# ALLPRINT-CAPBOARD-677512-HEAD-BOARD-COMM.net
KiCad netlist of a schematic drawn in Altium Designer
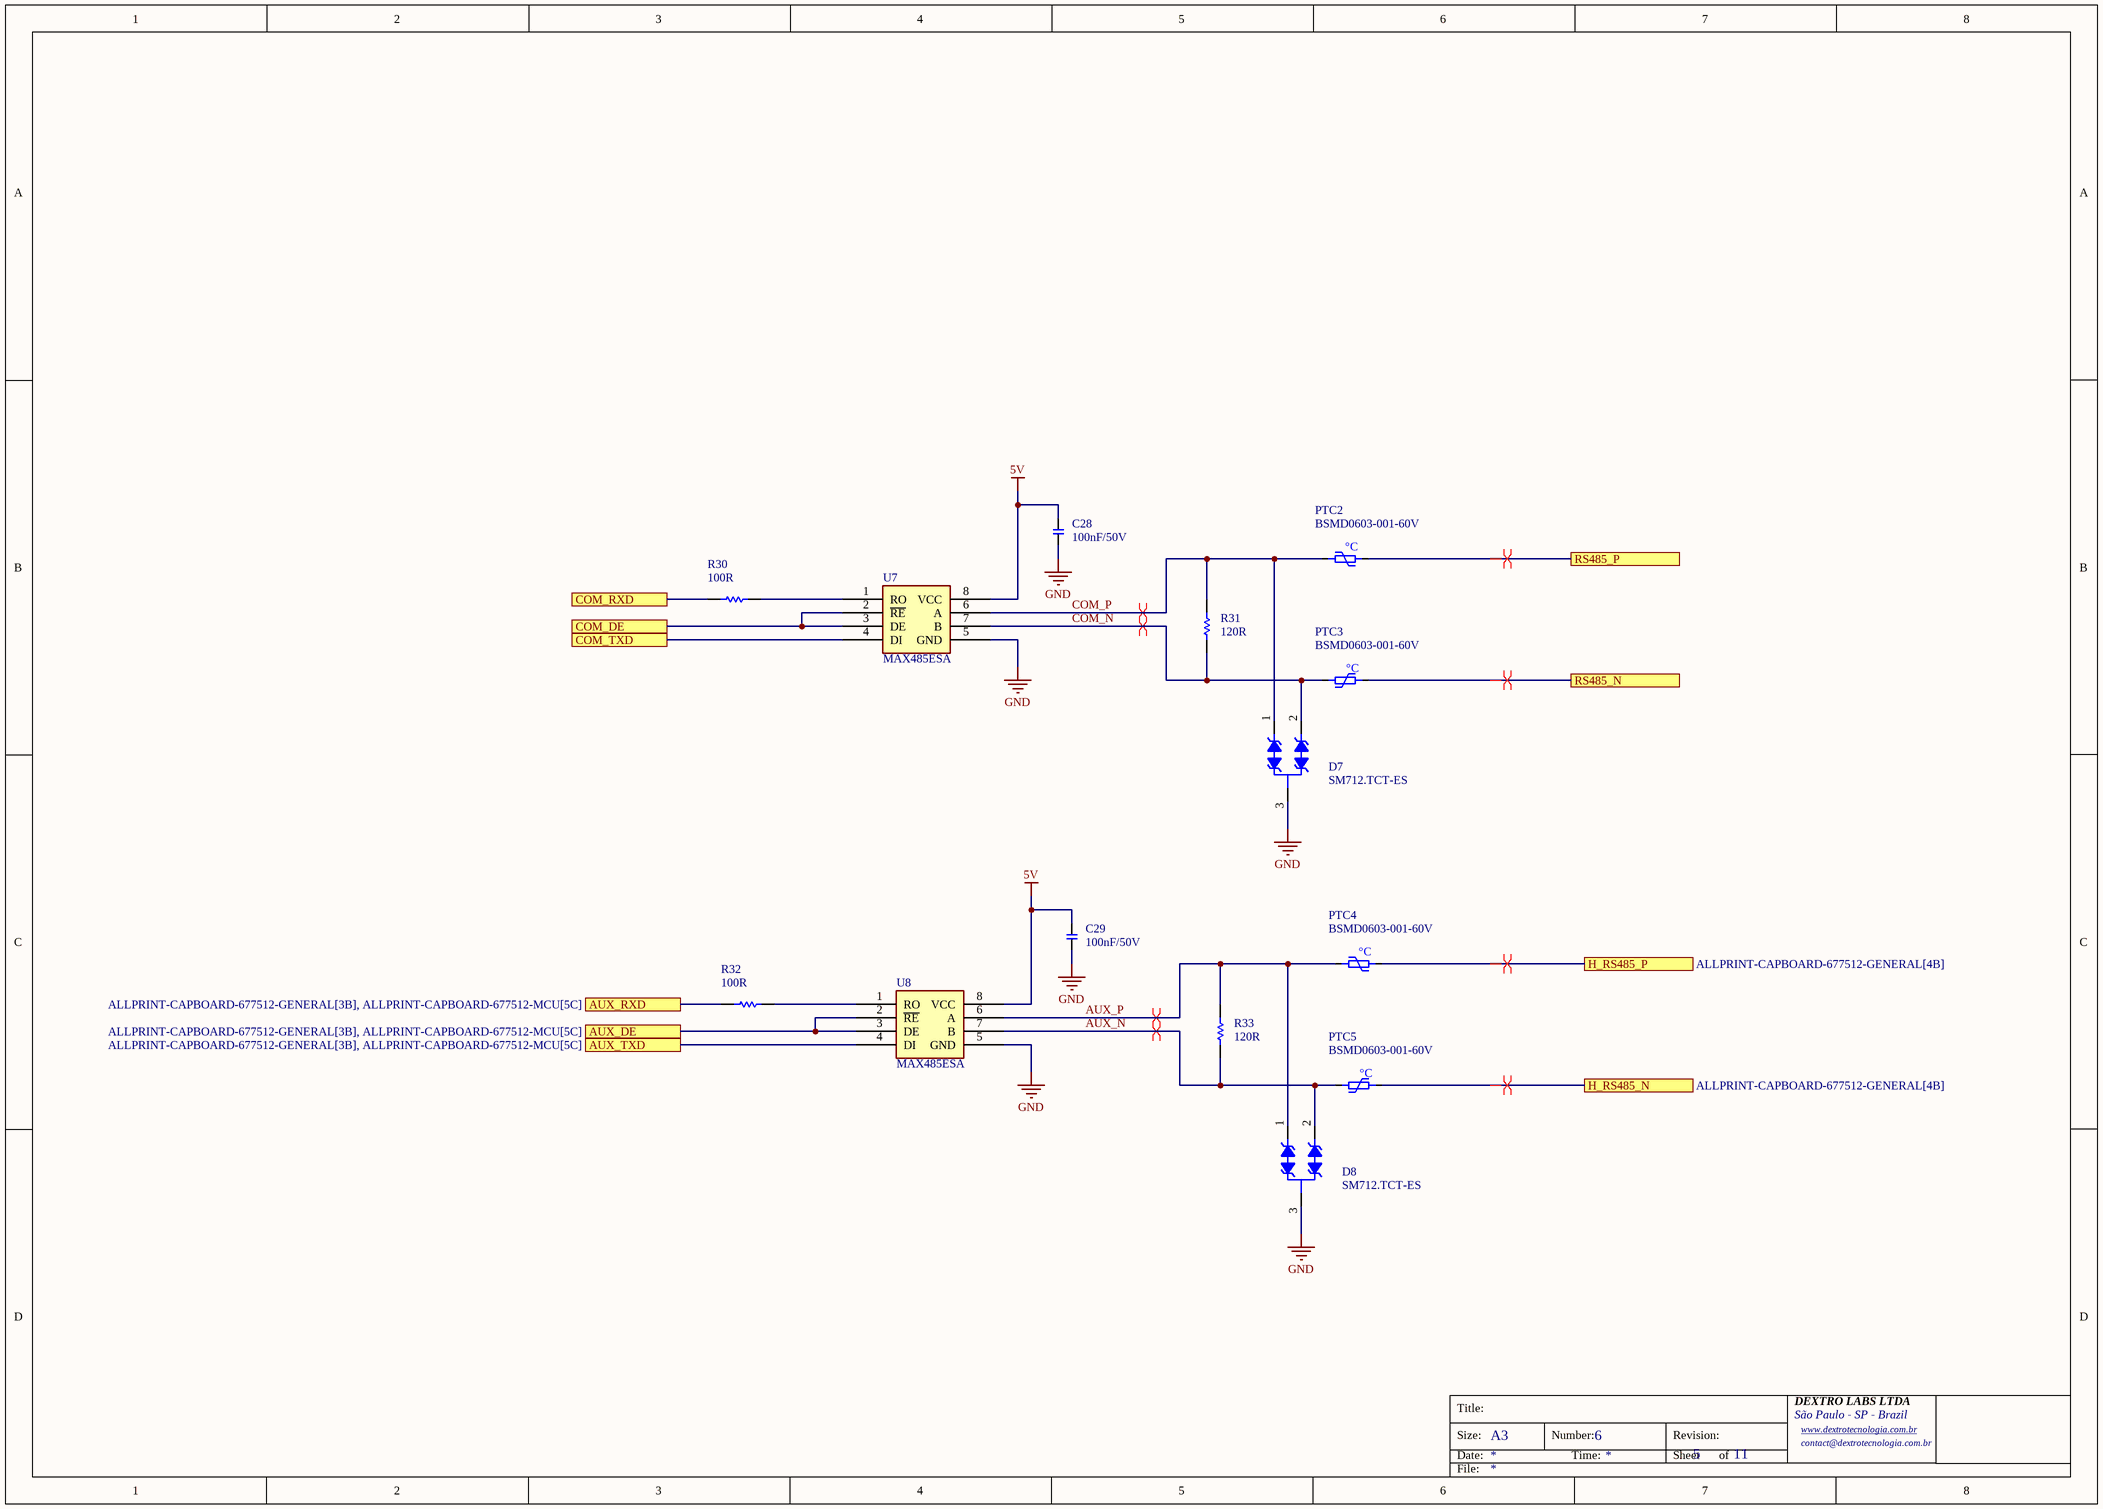
[diagram p0: ALLPRINT-CAPBOARD-677512-HEAD-BOARD-COMM.SchDoc]

(export (version "E")
  (design (tool "Eeschema 10.0.6"))
  (components
    (comp (ref "C28")
      (value "100nF/50V")
      (footprint "CAP-0603")
      (description "50V 100nF X7R ±10% 0603 Multilayer Ceramic Capacitors MLCC - SMD/SMT ROHS")
      (libsource (lib "dextro-labs") (part "CAP-100nF/50V-0603-X7R-MLCC"))
    )
    (comp (ref "C29")
      (value "100nF/50V")
      (footprint "CAP-0603")
      (description "50V 100nF X7R ±10% 0603 Multilayer Ceramic Capacitors MLCC - SMD/SMT ROHS")
      (libsource (lib "dextro-labs") (part "CAP-100nF/50V-0603-X7R-MLCC"))
    )
    (comp (ref "D7")
      (value "SM712.TCT-ES")
      (footprint "SOT23-3")
      (description "400W@8/20us Bidirectional SOT-23 ESD and Surge Protection (TVS/ESD) ROHS")
      (libsource (lib "dextro-labs") (part "SM712.TCT-ES"))
    )
    (comp (ref "D8")
      (value "SM712.TCT-ES")
      (footprint "SOT23-3")
      (description "400W@8/20us Bidirectional SOT-23 ESD and Surge Protection (TVS/ESD) ROHS")
      (libsource (lib "dextro-labs") (part "SM712.TCT-ES"))
    )
    (comp (ref "PTC2")
      (value "BSMD0603-001-60V")
      (footprint "PTC-0603")
      (description "60V 10mA 20A 50mA 15Ω 0603 PTC Resettable Fuses ROHS")
      (libsource (lib "dextro-labs") (part "PTC-FUSE-60V-10mA-0603"))
    )
    (comp (ref "PTC3")
      (value "BSMD0603-001-60V")
      (footprint "PTC-0603")
      (description "60V 10mA 20A 50mA 15Ω 0603 PTC Resettable Fuses ROHS")
      (libsource (lib "dextro-labs") (part "PTC-FUSE-60V-10mA-0603"))
    )
    (comp (ref "PTC4")
      (value "BSMD0603-001-60V")
      (footprint "PTC-0603")
      (description "60V 10mA 20A 50mA 15Ω 0603 PTC Resettable Fuses ROHS")
      (libsource (lib "dextro-labs") (part "PTC-FUSE-60V-10mA-0603"))
    )
    (comp (ref "PTC5")
      (value "BSMD0603-001-60V")
      (footprint "PTC-0603")
      (description "60V 10mA 20A 50mA 15Ω 0603 PTC Resettable Fuses ROHS")
      (libsource (lib "dextro-labs") (part "PTC-FUSE-60V-10mA-0603"))
    )
    (comp (ref "R30")
      (value "100R")
      (footprint "RES-0603")
      (description "100mW Thick Film Resistor 75V ±100ppm/℃ ±1% 100Ω 0603 Chip Resistor - Surface Mount ROHS")
      (libsource (lib "dextro-labs") (part "RES-100R-1%-100mW-0603"))
    )
    (comp (ref "R31")
      (value "120R")
      (footprint "RES-1206")
      (description "120Ω ±1% 500mW 1206 Thick Film Resistor")
      (libsource (lib "dextro-labs") (part "RES-120R-1%-500mW-1206"))
    )
    (comp (ref "R32")
      (value "100R")
      (footprint "RES-0603")
      (description "100mW Thick Film Resistor 75V ±100ppm/℃ ±1% 100Ω 0603 Chip Resistor - Surface Mount ROHS")
      (libsource (lib "dextro-labs") (part "RES-100R-1%-100mW-0603"))
    )
    (comp (ref "R33")
      (value "120R")
      (footprint "RES-1206")
      (description "120Ω ±1% 500mW 1206 Thick Film Resistor")
      (libsource (lib "dextro-labs") (part "RES-120R-1%-500mW-1206"))
    )
    (comp (ref "U7")
      (value "MAX485ESA")
      (footprint "SOIC-08")
      (description "Low-Power, Slew-Rate-Limited RS-485/RS-422 Transceivers")
      (libsource (lib "dextro-labs") (part "MAX485ESA"))
    )
    (comp (ref "U8")
      (value "MAX485ESA")
      (footprint "SOIC-08")
      (description "Low-Power, Slew-Rate-Limited RS-485/RS-422 Transceivers")
      (libsource (lib "dextro-labs") (part "MAX485ESA"))
    )
  )
  (nets
    (net (code "1") (name "/AUX_DE") (class "Default")
      (node (ref "U8") (pin "2") (pinfunction "~{RE}_2") (pintype "passive"))
      (node (ref "U8") (pin "3") (pinfunction "DE_3") (pintype "passive"))
    )
    (net (code "2") (name "/AUX_N") (class "Default")
      (node (ref "D8") (pin "2") (pinfunction "A2_2") (pintype "passive"))
      (node (ref "PTC5") (pin "2") (pinfunction "2_2") (pintype "passive"))
      (node (ref "R33") (pin "1") (pinfunction "1_1") (pintype "passive"))
      (node (ref "U8") (pin "7") (pinfunction "B_7") (pintype "passive"))
    )
    (net (code "3") (name "/AUX_P") (class "Default")
      (node (ref "D8") (pin "1") (pinfunction "A1_1") (pintype "passive"))
      (node (ref "PTC4") (pin "1") (pinfunction "1_1") (pintype "passive"))
      (node (ref "R33") (pin "2") (pinfunction "2_2") (pintype "passive"))
      (node (ref "U8") (pin "6") (pinfunction "A_6") (pintype "passive"))
    )
    (net (code "4") (name "/AUX_RXD") (class "Default")
      (node (ref "R32") (pin "1") (pinfunction "1_1") (pintype "passive"))
    )
    (net (code "5") (name "/AUX_TXD") (class "Default")
      (node (ref "U8") (pin "4") (pinfunction "DI_4") (pintype "passive"))
    )
    (net (code "6") (name "/COM_DE") (class "Default")
      (node (ref "U7") (pin "2") (pinfunction "~{RE}_2") (pintype "passive"))
      (node (ref "U7") (pin "3") (pinfunction "DE_3") (pintype "passive"))
    )
    (net (code "7") (name "/COM_N") (class "Default")
      (node (ref "D7") (pin "2") (pinfunction "A2_2") (pintype "passive"))
      (node (ref "PTC3") (pin "2") (pinfunction "2_2") (pintype "passive"))
      (node (ref "R31") (pin "1") (pinfunction "1_1") (pintype "passive"))
      (node (ref "U7") (pin "7") (pinfunction "B_7") (pintype "passive"))
    )
    (net (code "8") (name "/COM_P") (class "Default")
      (node (ref "D7") (pin "1") (pinfunction "A1_1") (pintype "passive"))
      (node (ref "PTC2") (pin "1") (pinfunction "1_1") (pintype "passive"))
      (node (ref "R31") (pin "2") (pinfunction "2_2") (pintype "passive"))
      (node (ref "U7") (pin "6") (pinfunction "A_6") (pintype "passive"))
    )
    (net (code "9") (name "/COM_RXD") (class "Default")
      (node (ref "R30") (pin "1") (pinfunction "1_1") (pintype "passive"))
    )
    (net (code "10") (name "/COM_TXD") (class "Default")
      (node (ref "U7") (pin "4") (pinfunction "DI_4") (pintype "passive"))
    )
    (net (code "11") (name "/H_RS485_N") (class "Default")
      (node (ref "PTC5") (pin "1") (pinfunction "1_1") (pintype "passive"))
    )
    (net (code "12") (name "/H_RS485_P") (class "Default")
      (node (ref "PTC4") (pin "2") (pinfunction "2_2") (pintype "passive"))
    )
    (net (code "13") (name "/RS485_N") (class "Default")
      (node (ref "PTC3") (pin "1") (pinfunction "1_1") (pintype "passive"))
    )
    (net (code "14") (name "/RS485_P") (class "Default")
      (node (ref "PTC2") (pin "2") (pinfunction "2_2") (pintype "passive"))
    )
    (net (code "15") (name "5V") (class "Default")
      (node (ref "C28") (pin "2") (pinfunction "2_2") (pintype "passive"))
      (node (ref "C29") (pin "2") (pinfunction "2_2") (pintype "passive"))
      (node (ref "U7") (pin "8") (pinfunction "VCC_8") (pintype "passive"))
      (node (ref "U8") (pin "8") (pinfunction "VCC_8") (pintype "passive"))
    )
    (net (code "16") (name "GND") (class "Default")
      (node (ref "C28") (pin "1") (pinfunction "1_1") (pintype "passive"))
      (node (ref "C29") (pin "1") (pinfunction "1_1") (pintype "passive"))
      (node (ref "D7") (pin "3") (pinfunction "K_3") (pintype "passive"))
      (node (ref "D8") (pin "3") (pinfunction "K_3") (pintype "passive"))
      (node (ref "U7") (pin "5") (pinfunction "GND_5") (pintype "passive"))
      (node (ref "U8") (pin "5") (pinfunction "GND_5") (pintype "passive"))
    )
    (net (code "17") (name "Net-(U7-RO)") (class "Default")
      (node (ref "R30") (pin "2") (pinfunction "2_2") (pintype "passive"))
      (node (ref "U7") (pin "1") (pinfunction "RO_1") (pintype "passive"))
    )
    (net (code "18") (name "Net-(U8-RO)") (class "Default")
      (node (ref "R32") (pin "2") (pinfunction "2_2") (pintype "passive"))
      (node (ref "U8") (pin "1") (pinfunction "RO_1") (pintype "passive"))
    )
  )
)
